# 5_-Motor_Driver_Schematic.net
KiCad netlist of a schematic drawn in Altium Designer
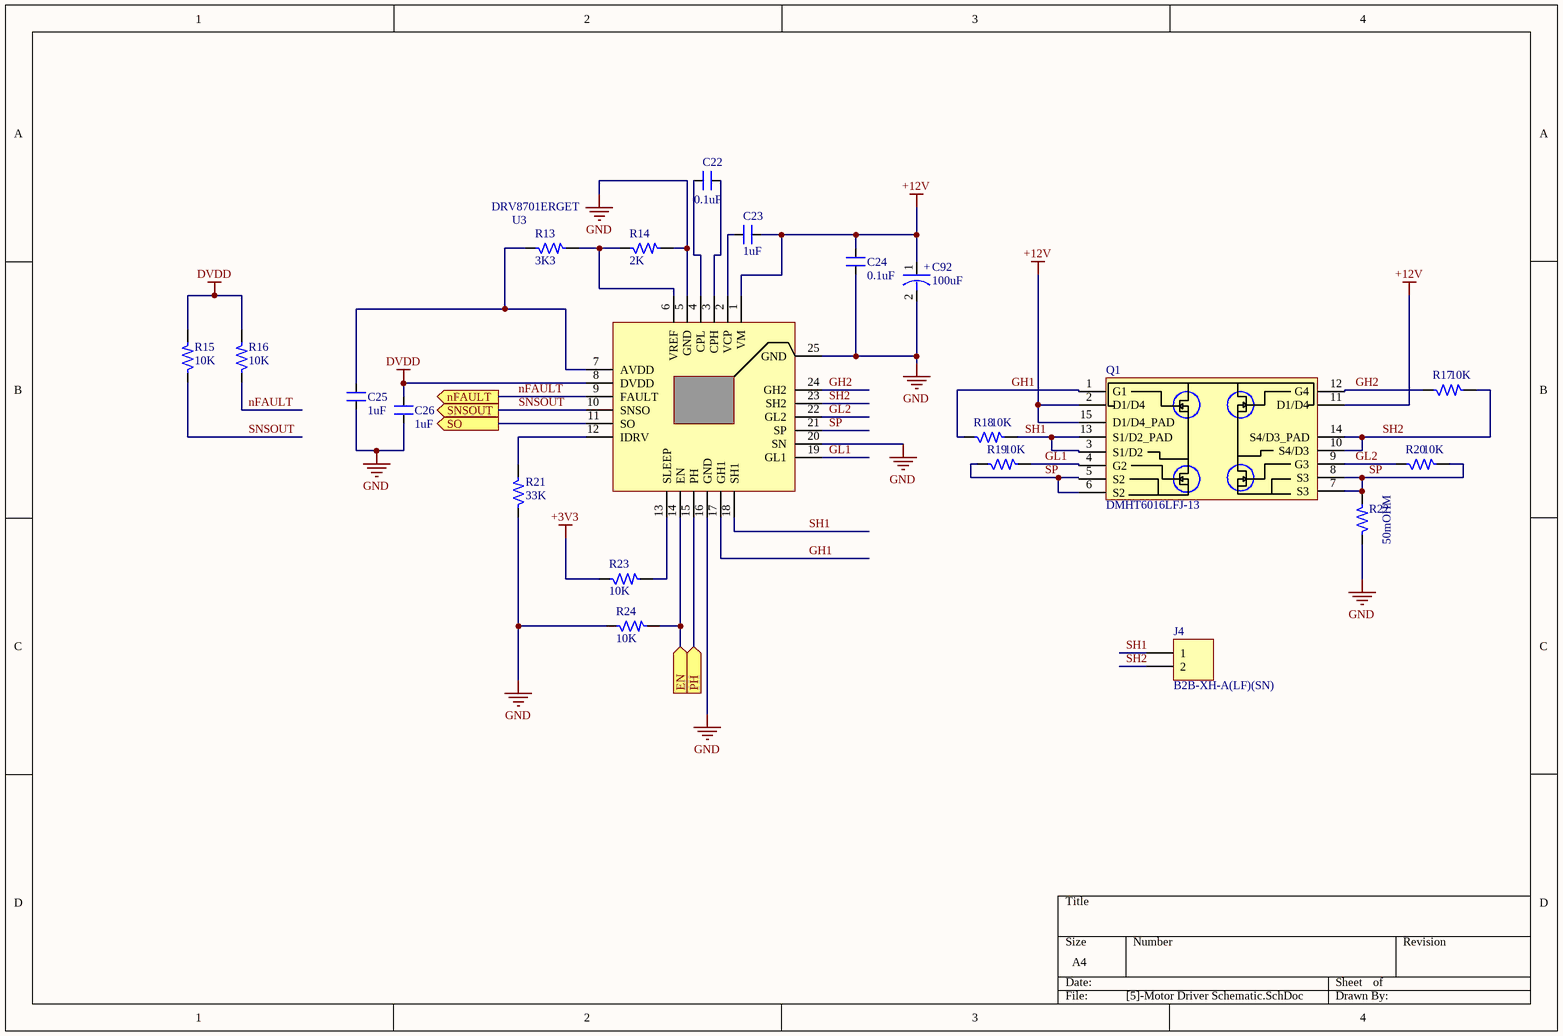
[diagram p0: [5]-Motor Driver Schematic.SchDoc]

(export (version "E")
  (design (tool "Eeschema 10.0.6"))
  (components
    (comp (ref "C22")
      (value "0.1uF")
      (footprint "CAP_0805")
      (description "0.1µF ±10% 50V Ceramic Capacitor X7R 0805 (2012 Metric)")
      (fields
        (field (name "MANUFACTURER") "Samsung")
        (field (name "MANUFACTURER PART NUMBER") "CL21B104KBCNNNC")
      )
      (libsource (lib "ESTEEMPCBLIB") (part "CAP_0.1uF-50V-10%-0805"))
    )
    (comp (ref "C23")
      (value "1uF")
      (footprint "CAP_0805")
      (description "1µF ±5% 50V Ceramic Capacitor X7R 0805 (2012 Metric)")
      (fields
        (field (name "MANUFACTURER") "Samsung")
        (field (name "MANUFACTURER PART NUMBER") "CC0805JKX7R9BB105")
      )
      (libsource (lib "ESTEEMPCBLIB") (part "CAP_1uF-50V-5%-0805"))
    )
    (comp (ref "C24")
      (value "0.1uF")
      (footprint "CAP_0805")
      (description "0.1µF ±10% 50V Ceramic Capacitor X7R 0805 (2012 Metric)")
      (fields
        (field (name "MANUFACTURER") "Samsung")
        (field (name "MANUFACTURER PART NUMBER") "CL21B104KBCNNNC")
      )
      (libsource (lib "ESTEEMPCBLIB") (part "CAP_0.1uF-50V-10%-0805"))
    )
    (comp (ref "C25")
      (value "1uF")
      (footprint "CAP_0805")
      (description "1µF ±5% 50V Ceramic Capacitor X7R 0805 (2012 Metric)")
      (fields
        (field (name "MANUFACTURER") "Samsung")
        (field (name "MANUFACTURER PART NUMBER") "CC0805JKX7R9BB105")
      )
      (libsource (lib "ESTEEMPCBLIB") (part "CAP_1uF-50V-5%-0805"))
    )
    (comp (ref "C26")
      (value "1uF")
      (footprint "CAP_0805")
      (description "1µF ±5% 50V Ceramic Capacitor X7R 0805 (2012 Metric)")
      (fields
        (field (name "MANUFACTURER") "Samsung")
        (field (name "MANUFACTURER PART NUMBER") "CC0805JKX7R9BB105")
      )
      (libsource (lib "ESTEEMPCBLIB") (part "CAP_1uF-50V-5%-0805"))
    )
    (comp (ref "C92")
      (value "100uF")
      (footprint "ACAP_P236_D305_H303_RAD")
      (description "100µF 25V Aluminum Electrolytic Capacitors Radial, Can - SMD 1000 Hrs @ 105°C")
      (fields
        (field (name "MANUFACTURER") "Nichicon")
        (field (name "MANUFACTURER PART NUMBER") "UWT1E101MCL1GS")
      )
      (libsource (lib "ESTEEMPCBLIB") (part "CAP-P_100uF-25V-20%-RAD"))
    )
    (comp (ref "J4")
      (value "B2B-XH-A(LF)(SN)")
      (footprint "CON2_100_B2B-XH-A_TH_ST")
      (description "2 Pins, 1 Row 2.54mm Pitch, Straight Connector, male")
      (fields (field (name "MANUFACTURER") "JST") (field (name "MATING PART NUMBER") "XHP-2"))
      (libsource (lib "ESTEEMPCBLIB") (part "CON-PLG_2X1-100-ST-TH"))
    )
    (comp (ref "Q1")
      (value "DMHT6016LFJ-13")
      (footprint "DFN5045-12_33_212_27X15_SMD_1")
      (description "Mosfet Array 4 N-Channel 14.8A (Ta) Surface Mount V-DFN5045-12")
      (fields (field (name "MANUFACTURER") "ON Semiconductor"))
      (libsource (lib "ESTEEMPCBLIB") (part "MOSFET-N_60V-14.8A-V-DFN5045-12"))
    )
    (comp (ref "R13")
      (value "3K3")
      (footprint "RES_0603")
      (description "3.3 kOhms ±1% 0.1W, 1/10W Chip Resistor 0603 (1608 Metric) Automotive AEC-Q200 Thick Film")
      (fields (field (name "MANUFACTURER") "Wilson") (field (name "MANUFACTURER PART NUMBER") "WR06X3301FTL"))
      (libsource (lib "ESTEEMPCBLIB") (part "RES_3.3K-0.1W-1%-0603"))
    )
    (comp (ref "R14")
      (value "2K")
      (footprint "RES_0603")
      (fields
        (field (name "MANUFACTURER") "Stackpole Electronics")
        (field (name "MANUFACTURER PART NUMBER") "RNCP0603FTD2K00")
      )
      (libsource (lib "ESTEEMPCBLIB") (part "RES_2K-0.125W-1%-0603"))
    )
    (comp (ref "R15")
      (value "10K")
      (footprint "RES_0603")
      (description "10 kOhms ±1% 0.1W, 1/10W Chip Resistor 0603 (1608 Metric) Automotive AEC-Q200 Thick Film")
      (fields (field (name "MANUFACTURER") "Walsin") (field (name "MANUFACTURER PART NUMBER") "WR06X1002FTL"))
      (libsource (lib "ESTEEMPCBLIB") (part "RES_10K-0.1W-1%-0603"))
    )
    (comp (ref "R16")
      (value "10K")
      (footprint "RES_0603")
      (description "10 kOhms ±1% 0.1W, 1/10W Chip Resistor 0603 (1608 Metric) Automotive AEC-Q200 Thick Film")
      (fields (field (name "MANUFACTURER") "Walsin") (field (name "MANUFACTURER PART NUMBER") "WR06X1002FTL"))
      (libsource (lib "ESTEEMPCBLIB") (part "RES_10K-0.1W-1%-0603"))
    )
    (comp (ref "R17")
      (value "10K")
      (footprint "RES_0603")
      (description "10 kOhms ±1% 0.1W, 1/10W Chip Resistor 0603 (1608 Metric) Automotive AEC-Q200 Thick Film")
      (fields (field (name "MANUFACTURER") "Walsin") (field (name "MANUFACTURER PART NUMBER") "WR06X1002FTL"))
      (libsource (lib "ESTEEMPCBLIB") (part "RES_10K-0.1W-1%-0603"))
    )
    (comp (ref "R18")
      (value "10K")
      (footprint "RES_0603")
      (description "10 kOhms ±1% 0.1W, 1/10W Chip Resistor 0603 (1608 Metric) Automotive AEC-Q200 Thick Film")
      (fields (field (name "MANUFACTURER") "Walsin") (field (name "MANUFACTURER PART NUMBER") "WR06X1002FTL"))
      (libsource (lib "ESTEEMPCBLIB") (part "RES_10K-0.1W-1%-0603"))
    )
    (comp (ref "R19")
      (value "10K")
      (footprint "RES_0603")
      (description "10 kOhms ±1% 0.1W, 1/10W Chip Resistor 0603 (1608 Metric) Automotive AEC-Q200 Thick Film")
      (fields (field (name "MANUFACTURER") "Walsin") (field (name "MANUFACTURER PART NUMBER") "WR06X1002FTL"))
      (libsource (lib "ESTEEMPCBLIB") (part "RES_10K-0.1W-1%-0603"))
    )
    (comp (ref "R20")
      (value "10K")
      (footprint "RES_0603")
      (description "10 kOhms ±1% 0.1W, 1/10W Chip Resistor 0603 (1608 Metric) Automotive AEC-Q200 Thick Film")
      (fields (field (name "MANUFACTURER") "Walsin") (field (name "MANUFACTURER PART NUMBER") "WR06X1002FTL"))
      (libsource (lib "ESTEEMPCBLIB") (part "RES_10K-0.1W-1%-0603"))
    )
    (comp (ref "R21")
      (value "33K")
      (footprint "RES_0805")
      (fields
        (field (name "MANUFACTURER") "Vishay BCcomponents")
        (field (name "MANUFACTURER PART NUMBER") "CRG0805F33K")
      )
      (libsource (lib "ESTEEMPCBLIB") (part "RES_33K-0.125W-1%-0805"))
    )
    (comp (ref "R22")
      (value "50mOHM")
      (footprint "RES_2512")
      (fields
        (field (name "MANUFACTURER") "Yageo")
        (field (name "MANUFACTURER PART NUMBER") "PA2512FKF7W0R05E")
      )
      (libsource (lib "ESTEEMPCBLIB") (part "RES_50mOhm-2W-1%-2512"))
    )
    (comp (ref "R23")
      (value "10K")
      (footprint "RES_0603")
      (description "10 kOhms ±1% 0.1W, 1/10W Chip Resistor 0603 (1608 Metric) Automotive AEC-Q200 Thick Film")
      (fields (field (name "MANUFACTURER") "Walsin") (field (name "MANUFACTURER PART NUMBER") "WR06X1002FTL"))
      (libsource (lib "ESTEEMPCBLIB") (part "RES_10K-0.1W-1%-0603"))
    )
    (comp (ref "R24")
      (value "10K")
      (footprint "RES_0603")
      (description "10 kOhms ±1% 0.1W, 1/10W Chip Resistor 0603 (1608 Metric) Automotive AEC-Q200 Thick Film")
      (fields (field (name "MANUFACTURER") "Walsin") (field (name "MANUFACTURER PART NUMBER") "WR06X1002FTL"))
      (libsource (lib "ESTEEMPCBLIB") (part "RES_10K-0.1W-1%-0603"))
    )
    (comp (ref "U3")
      (value "DRV8701ERGET")
      (footprint "VFQFN24_19.6_196_12X32_SMD_1")
      (description "Motor Driver Power MOSFET Parallel 24-VQFN (4x4)")
      (fields (field (name "MANUFACTURER") "Texas Instruments"))
      (libsource (lib "ESTEEMPCBLIB") (part "IC_DRV8701ERGET"))
    )
  )
  (nets
    (net (code "1") (name "+3V3") (class "Default")
      (node (ref "R23") (pin "1") (pinfunction "1_1") (pintype "passive"))
    )
    (net (code "2") (name "+12V") (class "Default")
      (node (ref "C23") (pin "2") (pinfunction "2_2") (pintype "passive"))
      (node (ref "C24") (pin "2") (pinfunction "2_2") (pintype "passive"))
      (node (ref "C92") (pin "1") (pinfunction "1_1") (pintype "passive"))
      (node (ref "Q1") (pin "11") (pinfunction "D1/D4_11") (pintype "passive"))
      (node (ref "Q1") (pin "15") (pinfunction "D1/D4_PAD_15") (pintype "passive"))
      (node (ref "Q1") (pin "2") (pinfunction "D1/D4_2") (pintype "passive"))
      (node (ref "U3") (pin "1") (pinfunction "VM_1") (pintype "passive"))
    )
    (net (code "3") (name "/EN") (class "Default")
      (node (ref "R24") (pin "2") (pinfunction "2_2") (pintype "passive"))
      (node (ref "U3") (pin "14") (pinfunction "EN_14") (pintype "passive"))
    )
    (net (code "4") (name "/GH1") (class "Default")
      (node (ref "Q1") (pin "1") (pinfunction "G1_1") (pintype "passive"))
      (node (ref "R18") (pin "1") (pinfunction "1_1") (pintype "passive"))
      (node (ref "U3") (pin "17") (pinfunction "GH1_17") (pintype "passive"))
    )
    (net (code "5") (name "/GH2") (class "Default")
      (node (ref "Q1") (pin "12") (pinfunction "G4_12") (pintype "passive"))
      (node (ref "R17") (pin "1") (pinfunction "1_1") (pintype "passive"))
      (node (ref "U3") (pin "24") (pinfunction "GH2_24") (pintype "passive"))
    )
    (net (code "6") (name "/GL1") (class "Default")
      (node (ref "Q1") (pin "4") (pinfunction "G2_4") (pintype "passive"))
      (node (ref "R19") (pin "2") (pinfunction "2_2") (pintype "passive"))
      (node (ref "U3") (pin "19") (pinfunction "GL1_19") (pintype "passive"))
    )
    (net (code "7") (name "/GL2") (class "Default")
      (node (ref "Q1") (pin "9") (pinfunction "G3_9") (pintype "passive"))
      (node (ref "R20") (pin "1") (pinfunction "1_1") (pintype "passive"))
      (node (ref "U3") (pin "22") (pinfunction "GL2_22") (pintype "passive"))
    )
    (net (code "8") (name "/PH") (class "Default")
      (node (ref "U3") (pin "15") (pinfunction "PH_15") (pintype "passive"))
    )
    (net (code "9") (name "/SH1") (class "Default")
      (node (ref "J4") (pin "1") (pinfunction "1_1") (pintype "passive"))
      (node (ref "Q1") (pin "13") (pinfunction "S1/D2_PAD_13") (pintype "passive"))
      (node (ref "Q1") (pin "3") (pinfunction "S1/D2_3") (pintype "passive"))
      (node (ref "R18") (pin "2") (pinfunction "2_2") (pintype "passive"))
      (node (ref "U3") (pin "18") (pinfunction "SH1_18") (pintype "passive"))
    )
    (net (code "10") (name "/SH2") (class "Default")
      (node (ref "J4") (pin "2") (pinfunction "2_2") (pintype "passive"))
      (node (ref "Q1") (pin "10") (pinfunction "S4/D3_10") (pintype "passive"))
      (node (ref "Q1") (pin "14") (pinfunction "S4/D3_PAD_14") (pintype "passive"))
      (node (ref "R17") (pin "2") (pinfunction "2_2") (pintype "passive"))
      (node (ref "U3") (pin "23") (pinfunction "SH2_23") (pintype "passive"))
    )
    (net (code "11") (name "/SNSOUT") (class "Default")
      (node (ref "R15") (pin "1") (pinfunction "1_1") (pintype "passive"))
      (node (ref "U3") (pin "10") (pinfunction "SNSO_10") (pintype "passive"))
    )
    (net (code "12") (name "/SO") (class "Default")
      (node (ref "U3") (pin "11") (pinfunction "SO_11") (pintype "passive"))
    )
    (net (code "13") (name "/SP") (class "Default")
      (node (ref "Q1") (pin "6") (pinfunction "S2_6") (pintype "passive"))
      (node (ref "Q1") (pin "7") (pinfunction "S3_7") (pintype "passive"))
      (node (ref "Q1") (pin "8") (pinfunction "S3_8") (pintype "passive"))
      (node (ref "R19") (pin "1") (pinfunction "1_1") (pintype "passive"))
      (node (ref "R20") (pin "2") (pinfunction "2_2") (pintype "passive"))
      (node (ref "R22") (pin "2") (pinfunction "2_2") (pintype "passive"))
      (node (ref "U3") (pin "21") (pinfunction "SP_21") (pintype "passive"))
    )
    (net (code "14") (name "/nFAULT") (class "Default")
      (node (ref "R16") (pin "1") (pinfunction "1_1") (pintype "passive"))
      (node (ref "U3") (pin "9") (pinfunction "FAULT_9") (pintype "passive"))
    )
    (net (code "15") (name "DVDD") (class "Default")
      (node (ref "C26") (pin "2") (pinfunction "2_2") (pintype "passive"))
      (node (ref "R15") (pin "2") (pinfunction "2_2") (pintype "passive"))
      (node (ref "R16") (pin "2") (pinfunction "2_2") (pintype "passive"))
      (node (ref "U3") (pin "8") (pinfunction "DVDD_8") (pintype "passive"))
    )
    (net (code "16") (name "GND") (class "Default")
      (node (ref "C24") (pin "1") (pinfunction "1_1") (pintype "passive"))
      (node (ref "C25") (pin "1") (pinfunction "1_1") (pintype "passive"))
      (node (ref "C26") (pin "1") (pinfunction "1_1") (pintype "passive"))
      (node (ref "C92") (pin "2") (pinfunction "2_2") (pintype "passive"))
      (node (ref "R14") (pin "2") (pinfunction "2_2") (pintype "passive"))
      (node (ref "R21") (pin "1") (pinfunction "1_1") (pintype "passive"))
      (node (ref "R22") (pin "1") (pinfunction "1_1") (pintype "passive"))
      (node (ref "R24") (pin "1") (pinfunction "1_1") (pintype "passive"))
      (node (ref "U3") (pin "16") (pinfunction "GND_16") (pintype "passive"))
      (node (ref "U3") (pin "20") (pinfunction "SN_20") (pintype "passive"))
      (node (ref "U3") (pin "25") (pinfunction "GND_25") (pintype "passive"))
      (node (ref "U3") (pin "5") (pinfunction "GND_5") (pintype "passive"))
    )
    (net (code "17") (name "Net-(U3-AVDD)") (class "Default")
      (node (ref "C25") (pin "2") (pinfunction "2_2") (pintype "passive"))
      (node (ref "R13") (pin "1") (pinfunction "1_1") (pintype "passive"))
      (node (ref "U3") (pin "7") (pinfunction "AVDD_7") (pintype "passive"))
    )
    (net (code "18") (name "Net-(U3-CPH)") (class "Default")
      (node (ref "C22") (pin "1") (pinfunction "1_1") (pintype "passive"))
      (node (ref "U3") (pin "3") (pinfunction "CPH_3") (pintype "passive"))
    )
    (net (code "19") (name "Net-(U3-CPL)") (class "Default")
      (node (ref "C22") (pin "2") (pinfunction "2_2") (pintype "passive"))
      (node (ref "U3") (pin "4") (pinfunction "CPL_4") (pintype "passive"))
    )
    (net (code "20") (name "Net-(U3-IDRV)") (class "Default")
      (node (ref "R21") (pin "2") (pinfunction "2_2") (pintype "passive"))
      (node (ref "U3") (pin "12") (pinfunction "IDRV_12") (pintype "passive"))
    )
    (net (code "21") (name "Net-(U3-SLEEP)") (class "Default")
      (node (ref "R23") (pin "2") (pinfunction "2_2") (pintype "passive"))
      (node (ref "U3") (pin "13") (pinfunction "SLEEP_13") (pintype "passive"))
    )
    (net (code "22") (name "Net-(U3-VCP)") (class "Default")
      (node (ref "C23") (pin "1") (pinfunction "1_1") (pintype "passive"))
      (node (ref "U3") (pin "2") (pinfunction "VCP_2") (pintype "passive"))
    )
    (net (code "23") (name "Net-(U3-VREF)") (class "Default")
      (node (ref "R13") (pin "2") (pinfunction "2_2") (pintype "passive"))
      (node (ref "R14") (pin "1") (pinfunction "1_1") (pintype "passive"))
      (node (ref "U3") (pin "6") (pinfunction "VREF_6") (pintype "passive"))
    )
    (net (code "24") (name "unconnected-(Q1-S2-Pad5)") (class "Default")
      (node (ref "Q1") (pin "5") (pinfunction "S2_5") (pintype "passive"))
    )
  )
)
